# Connectors.net
KiCad netlist of a schematic drawn in Altium Designer
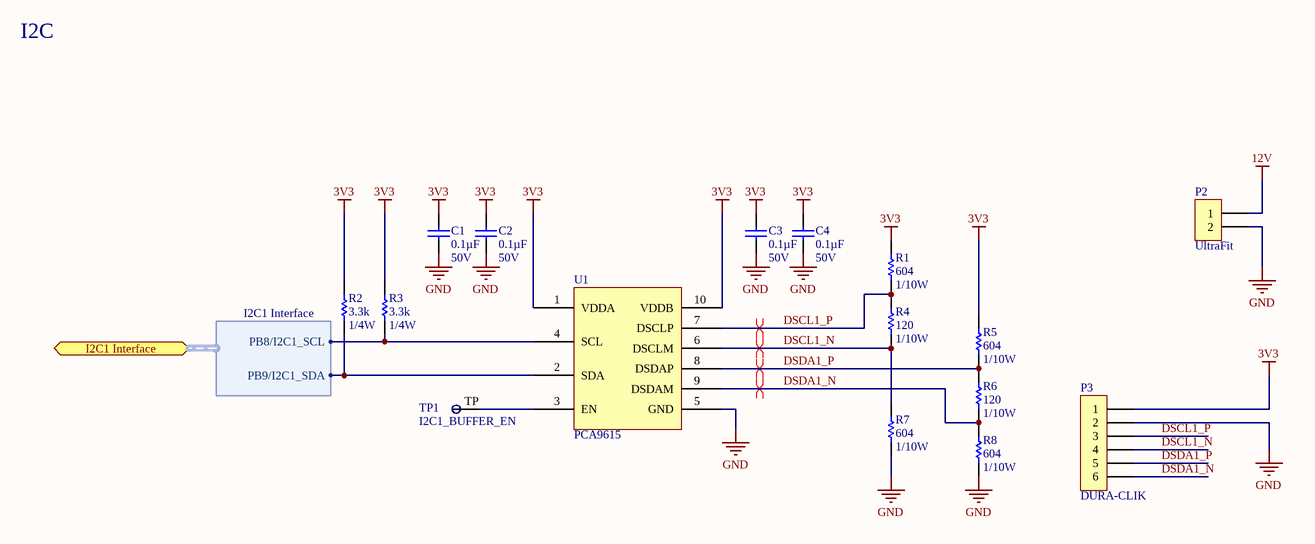
[diagram p0: Connectors.SchDoc]

(export (version "E")
  (design (tool "Eeschema 10.0.6"))
  (components
    (comp (ref "C1")
      (value "CAP CER 0.1UF 50V 10% X7R 0603")
      (footprint "CAP, 0603")
      (description "0.10µF ±10% 50V Ceramic Capacitor X7R 0603 (1608 Metric)")
      (fields
        (field (name "TOLERANCE") "±10%")
        (field (name "CAPACITANCE") "0.1µF")
        (field (name "VOLTAGE") "50V")
      )
      (libsource (lib "Schematic Diagrams") (part "CAP CER 0.1UF 50V 10% X7R 0603"))
    )
    (comp (ref "C2")
      (value "CAP CER 0.1UF 50V 10% X7R 0603")
      (footprint "CAP, 0603")
      (description "0.10µF ±10% 50V Ceramic Capacitor X7R 0603 (1608 Metric)")
      (fields
        (field (name "TOLERANCE") "±10%")
        (field (name "CAPACITANCE") "0.1µF")
        (field (name "VOLTAGE") "50V")
      )
      (libsource (lib "Schematic Diagrams") (part "CAP CER 0.1UF 50V 10% X7R 0603"))
    )
    (comp (ref "C3")
      (value "CAP CER 0.1UF 50V 10% X7R 0603")
      (footprint "CAP, 0603")
      (description "0.10µF ±10% 50V Ceramic Capacitor X7R 0603 (1608 Metric)")
      (fields
        (field (name "TOLERANCE") "±10%")
        (field (name "CAPACITANCE") "0.1µF")
        (field (name "VOLTAGE") "50V")
      )
      (libsource (lib "Schematic Diagrams") (part "CAP CER 0.1UF 50V 10% X7R 0603"))
    )
    (comp (ref "C4")
      (value "CAP CER 0.1UF 50V 10% X7R 0603")
      (footprint "CAP, 0603")
      (description "0.10µF ±10% 50V Ceramic Capacitor X7R 0603 (1608 Metric)")
      (fields
        (field (name "TOLERANCE") "±10%")
        (field (name "CAPACITANCE") "0.1µF")
        (field (name "VOLTAGE") "50V")
      )
      (libsource (lib "Schematic Diagrams") (part "CAP CER 0.1UF 50V 10% X7R 0603"))
    )
    (comp (ref "P2")
      (value "CONN 2POS ULTRA-FIT 0.138\"")
      (footprint "CONN, 2POS ULTRA-FIT")
      (description "2 Positions Header, Shrouded Connector 0.138\" (3.50mm) Through Hole Gold")
      (fields (field (name "VOLTAGE") "400V") (field (name "SERIES") "UltraFit"))
      (libsource (lib "Schematic Diagrams") (part "CONN 2POS ULTRA-FIT 0.138{dblquote}"))
    )
    (comp (ref "P3")
      (value "DURA-CLIK")
      (footprint "CONN, 6POS DURA-CLIK VERT")
      (description "6 Positions Header, Shrouded Connector 0.079\" (2.00mm) Surface Mount, Vertical Tin")
      (fields (field (name "MANUFACTURER") "Molex") (field (name "MANUFACTURER PART NUMBER") "5600200820"))
      (libsource (lib "Schematic Diagrams") (part "CONN 6POS DURA-CLIK 0.079{dblquote}"))
    )
    (comp (ref "R1")
      (value "RES 604 OHM 1% 1/10W 0603")
      (footprint "RES, 0603")
      (description "RES SMD 604 OHM 1% 1/10W 0603")
      (fields
        (field (name "TOLERANCE") "±1%")
        (field (name "RESISTANCE") "604")
        (field (name "POWER") "1/10W")
      )
      (libsource (lib "Schematic Diagrams") (part "RES 604 OHM 1% 1/10W 0603"))
    )
    (comp (ref "R2")
      (value "RES 3.3K OHM 1% 1/4W 0603")
      (footprint "RES, 0603")
      (fields
        (field (name "TOLERANCE") "±1%")
        (field (name "RESISTANCE") "3.3k")
        (field (name "POWER") "1/4W")
      )
      (libsource (lib "Schematic Diagrams") (part "RES 3.3K OHM 1% 1/4W 0603"))
    )
    (comp (ref "R3")
      (value "RES 3.3K OHM 1% 1/4W 0603")
      (footprint "RES, 0603")
      (fields
        (field (name "TOLERANCE") "±1%")
        (field (name "RESISTANCE") "3.3k")
        (field (name "POWER") "1/4W")
      )
      (libsource (lib "Schematic Diagrams") (part "RES 3.3K OHM 1% 1/4W 0603"))
    )
    (comp (ref "R4")
      (value "RES 120 OHM 1% 1/10W 0603")
      (footprint "RES, 0603")
      (description "RES SMD 120 OHM 1% 1/10W 0603")
      (fields
        (field (name "TOLERANCE") "±1%")
        (field (name "RESISTANCE") "120")
        (field (name "POWER") "1/10W")
      )
      (libsource (lib "Schematic Diagrams") (part "RES 120 OHM 1% 1/10W 0603"))
    )
    (comp (ref "R5")
      (value "RES 604 OHM 1% 1/10W 0603")
      (footprint "RES, 0603")
      (description "RES SMD 604 OHM 1% 1/10W 0603")
      (fields
        (field (name "TOLERANCE") "±1%")
        (field (name "RESISTANCE") "604")
        (field (name "POWER") "1/10W")
      )
      (libsource (lib "Schematic Diagrams") (part "RES 604 OHM 1% 1/10W 0603"))
    )
    (comp (ref "R6")
      (value "RES 120 OHM 1% 1/10W 0603")
      (footprint "RES, 0603")
      (description "RES SMD 120 OHM 1% 1/10W 0603")
      (fields
        (field (name "TOLERANCE") "±1%")
        (field (name "RESISTANCE") "120")
        (field (name "POWER") "1/10W")
      )
      (libsource (lib "Schematic Diagrams") (part "RES 120 OHM 1% 1/10W 0603"))
    )
    (comp (ref "R7")
      (value "RES 604 OHM 1% 1/10W 0603")
      (footprint "RES, 0603")
      (description "RES SMD 604 OHM 1% 1/10W 0603")
      (fields
        (field (name "TOLERANCE") "±1%")
        (field (name "RESISTANCE") "604")
        (field (name "POWER") "1/10W")
      )
      (libsource (lib "Schematic Diagrams") (part "RES 604 OHM 1% 1/10W 0603"))
    )
    (comp (ref "R8")
      (value "RES 604 OHM 1% 1/10W 0603")
      (footprint "RES, 0603")
      (description "RES SMD 604 OHM 1% 1/10W 0603")
      (fields
        (field (name "TOLERANCE") "±1%")
        (field (name "RESISTANCE") "604")
        (field (name "POWER") "1/10W")
      )
      (libsource (lib "Schematic Diagrams") (part "RES 604 OHM 1% 1/10W 0603"))
    )
    (comp (ref "TP1")
      (value "I2C1_BUFFER_EN")
      (footprint "Test Point")
      (libsource (lib "Schematic Diagrams") (part "Test Point"))
    )
    (comp (ref "U1")
      (value "IC DIFFERENTIAL I2C BUFFER PCA9615")
      (footprint "TSSOP50P490X110-10N")
      (description "Buffer, ReDriver 2 Channel 400kHz 10-TSSOP")
      (fields
        (field (name "MANUFACTURER") "NXP USA Inc.")
        (field (name "MANUFACTURER PART NUMBER") "PCA9615DPJ")
        (field (name "BASE PART NUMBER") "PCA9615")
      )
      (libsource (lib "Schematic Diagrams") (part "IC DIFFERENTIAL I2C BUFFER PCA9615"))
    )
  )
  (nets
    (net (code "3") (name "/DSCL1_N") (class "Default")
      (node (ref "P3") (pin "4") (pinfunction "4_4") (pintype "passive"))
      (node (ref "R4") (pin "2") (pinfunction "2_2") (pintype "passive"))
      (node (ref "R7") (pin "1") (pinfunction "1_1") (pintype "passive"))
      (node (ref "U1") (pin "6") (pinfunction "DSCLM_6") (pintype "passive"))
    )
    (net (code "4") (name "/DSCL1_P") (class "Default")
      (node (ref "P3") (pin "3") (pinfunction "3_3") (pintype "passive"))
      (node (ref "R1") (pin "2") (pinfunction "2_2") (pintype "passive"))
      (node (ref "R4") (pin "1") (pinfunction "1_1") (pintype "passive"))
      (node (ref "U1") (pin "7") (pinfunction "DSCLP_7") (pintype "passive"))
    )
    (net (code "5") (name "/DSDA1_N") (class "Default")
      (node (ref "P3") (pin "6") (pinfunction "6_6") (pintype "passive"))
      (node (ref "R6") (pin "2") (pinfunction "2_2") (pintype "passive"))
      (node (ref "R8") (pin "1") (pinfunction "1_1") (pintype "passive"))
      (node (ref "U1") (pin "9") (pinfunction "DSDAM_9") (pintype "passive"))
    )
    (net (code "6") (name "/DSDA1_P") (class "Default")
      (node (ref "P3") (pin "5") (pinfunction "5_5") (pintype "passive"))
      (node (ref "R5") (pin "2") (pinfunction "2_2") (pintype "passive"))
      (node (ref "R6") (pin "1") (pinfunction "1_1") (pintype "passive"))
      (node (ref "U1") (pin "8") (pinfunction "DSDAP_8") (pintype "passive"))
    )
    (net (code "8") (name "3V3") (class "Default")
      (node (ref "C1") (pin "1") (pinfunction "1_1") (pintype "passive"))
      (node (ref "C2") (pin "1") (pinfunction "1_1") (pintype "passive"))
      (node (ref "C3") (pin "1") (pinfunction "1_1") (pintype "passive"))
      (node (ref "C4") (pin "1") (pinfunction "1_1") (pintype "passive"))
      (node (ref "P3") (pin "1") (pinfunction "1_1") (pintype "passive"))
      (node (ref "R1") (pin "1") (pinfunction "1_1") (pintype "passive"))
      (node (ref "R2") (pin "1") (pinfunction "1_1") (pintype "passive"))
      (node (ref "R3") (pin "1") (pinfunction "1_1") (pintype "passive"))
      (node (ref "R5") (pin "1") (pinfunction "1_1") (pintype "passive"))
      (node (ref "U1") (pin "1") (pinfunction "VDDA_1") (pintype "passive"))
      (node (ref "U1") (pin "10") (pinfunction "VDDB_10") (pintype "passive"))
    )
    (net (code "9") (name "12V") (class "Default")
      (node (ref "P2") (pin "1") (pinfunction "1_1") (pintype "passive"))
    )
    (net (code "10") (name "GND") (class "Default")
      (node (ref "C1") (pin "2") (pinfunction "2_2") (pintype "passive"))
      (node (ref "C2") (pin "2") (pinfunction "2_2") (pintype "passive"))
      (node (ref "C3") (pin "2") (pinfunction "2_2") (pintype "passive"))
      (node (ref "C4") (pin "2") (pinfunction "2_2") (pintype "passive"))
      (node (ref "P2") (pin "2") (pinfunction "2_2") (pintype "passive"))
      (node (ref "P3") (pin "2") (pinfunction "2_2") (pintype "passive"))
      (node (ref "R7") (pin "2") (pinfunction "2_2") (pintype "passive"))
      (node (ref "R8") (pin "2") (pinfunction "2_2") (pintype "passive"))
      (node (ref "U1") (pin "5") (pinfunction "GND_5") (pintype "passive"))
    )
    (net (code "11") (name "Net-(TP1-1)") (class "Default")
      (node (ref "TP1") (pin "TP") (pinfunction "1_TP") (pintype "passive"))
      (node (ref "U1") (pin "3") (pinfunction "EN_3") (pintype "passive"))
    )
    (net (code "12") (name "Net-(U1-SCL)") (class "Default")
      (node (ref "R3") (pin "2") (pinfunction "2_2") (pintype "passive"))
      (node (ref "U1") (pin "4") (pinfunction "SCL_4") (pintype "passive"))
    )
    (net (code "13") (name "Net-(U1-SDA)") (class "Default")
      (node (ref "R2") (pin "2") (pinfunction "2_2") (pintype "passive"))
      (node (ref "U1") (pin "2") (pinfunction "SDA_2") (pintype "passive"))
    )
  )
)
